# R303D.net
KiCad netlist of a schematic drawn in EAGLE
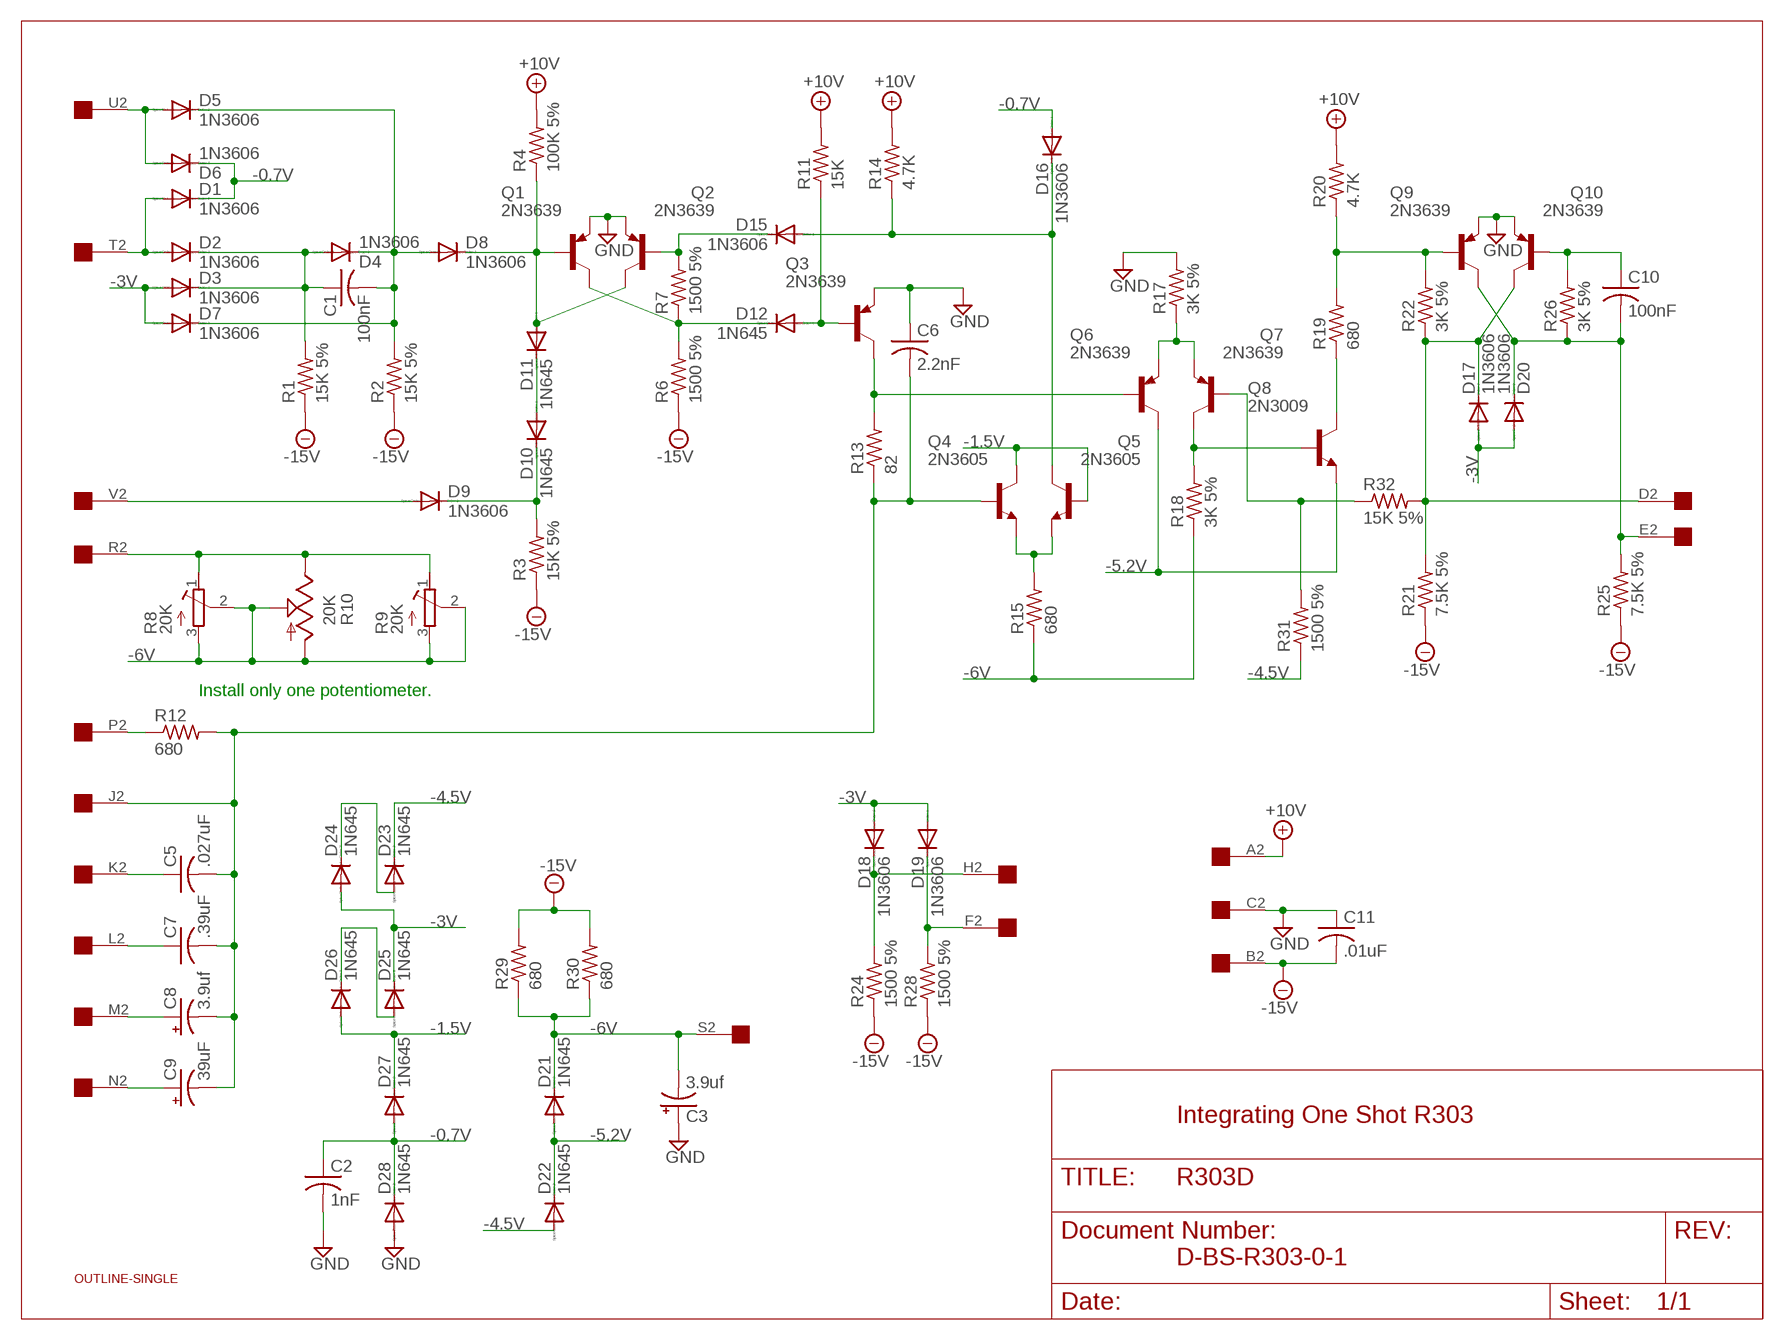
[diagram p0: schematic, sheet 1]

(export (version "E")
  (design (tool "Eeschema 10.0.6"))
  (components
    (comp (ref "C1")
      (value "100nF")
      (footprint "eagle-import:C075-032X103")
      (libsource (lib "eagle-import") (part "C-US075-032X103"))
    )
    (comp (ref "C2")
      (value "1nF")
      (footprint "eagle-import:C050-025X075")
      (libsource (lib "eagle-import") (part "C-US050-025X075"))
    )
    (comp (ref "C3")
      (value "3.9uf")
      (footprint "eagle-import:E12-4")
      (libsource (lib "eagle-import") (part "CPOL-USE12-4AXIAL"))
    )
    (comp (ref "C5")
      (value ".027uF")
      (footprint "eagle-import:C225-062X268")
      (libsource (lib "eagle-import") (part "C-US225-062X268"))
    )
    (comp (ref "C6")
      (value "2.2nF")
      (footprint "eagle-import:C050-025X075")
      (libsource (lib "eagle-import") (part "C-US050-025X075"))
    )
    (comp (ref "C7")
      (value ".39uF")
      (footprint "eagle-import:C325-137X374")
      (libsource (lib "eagle-import") (part "C-US325-137X374"))
    )
    (comp (ref "C8")
      (value "3.9uf")
      (footprint "eagle-import:E12-4")
      (libsource (lib "eagle-import") (part "CPOL-USE12-4AXIAL"))
    )
    (comp (ref "C9")
      (value "39uF")
      (footprint "eagle-import:E15-5")
      (libsource (lib "eagle-import") (part "CPOL-USE15-5AXIAL"))
    )
    (comp (ref "C10")
      (value "100nF")
      (footprint "eagle-import:C075-032X103")
      (libsource (lib "eagle-import") (part "C-US075-032X103"))
    )
    (comp (ref "C11")
      (value ".01uF")
      (footprint "eagle-import:C075-032X103")
      (libsource (lib "eagle-import") (part "C-US075-032X103"))
    )
    (comp (ref "D1")
      (value "1N3606")
      (footprint "eagle-import:DO35-10")
      (libsource (lib "eagle-import") (part "1N4148DO35-10"))
    )
    (comp (ref "D2")
      (value "1N3606")
      (footprint "eagle-import:DO35-10")
      (libsource (lib "eagle-import") (part "1N4148DO35-10"))
    )
    (comp (ref "D3")
      (value "1N3606")
      (footprint "eagle-import:DO35-10")
      (libsource (lib "eagle-import") (part "1N4148DO35-10"))
    )
    (comp (ref "D4")
      (value "1N3606")
      (footprint "eagle-import:DO35-10")
      (libsource (lib "eagle-import") (part "1N4148DO35-10"))
    )
    (comp (ref "D5")
      (value "1N3606")
      (footprint "eagle-import:DO35-10")
      (libsource (lib "eagle-import") (part "1N4148DO35-10"))
    )
    (comp (ref "D6")
      (value "1N3606")
      (footprint "eagle-import:DO35-10")
      (libsource (lib "eagle-import") (part "1N4148DO35-10"))
    )
    (comp (ref "D7")
      (value "1N3606")
      (footprint "eagle-import:DO35-10")
      (libsource (lib "eagle-import") (part "1N4148DO35-10"))
    )
    (comp (ref "D8")
      (value "1N3606")
      (footprint "eagle-import:DO35-10")
      (libsource (lib "eagle-import") (part "1N4148DO35-10"))
    )
    (comp (ref "D9")
      (value "1N3606")
      (footprint "eagle-import:DO35-10")
      (libsource (lib "eagle-import") (part "1N4148DO35-10"))
    )
    (comp (ref "D10")
      (value "1N645")
      (footprint "eagle-import:DO35-10")
      (libsource (lib "eagle-import") (part "1N4148DO35-10"))
    )
    (comp (ref "D11")
      (value "1N645")
      (footprint "eagle-import:DO35-10")
      (libsource (lib "eagle-import") (part "1N4148DO35-10"))
    )
    (comp (ref "D12")
      (value "1N645")
      (footprint "eagle-import:DO35-10")
      (libsource (lib "eagle-import") (part "1N4148DO35-10"))
    )
    (comp (ref "D15")
      (value "1N3606")
      (footprint "eagle-import:DO35-10")
      (libsource (lib "eagle-import") (part "1N4148DO35-10"))
    )
    (comp (ref "D16")
      (value "1N3606")
      (footprint "eagle-import:DO35-10")
      (libsource (lib "eagle-import") (part "1N4148DO35-10"))
    )
    (comp (ref "D17")
      (value "1N3606")
      (footprint "eagle-import:DO35-10")
      (libsource (lib "eagle-import") (part "1N4148DO35-10"))
    )
    (comp (ref "D18")
      (value "1N3606")
      (footprint "eagle-import:DO35-10")
      (libsource (lib "eagle-import") (part "1N4148DO35-10"))
    )
    (comp (ref "D19")
      (value "1N3606")
      (footprint "eagle-import:DO35-10")
      (libsource (lib "eagle-import") (part "1N4148DO35-10"))
    )
    (comp (ref "D20")
      (value "1N3606")
      (footprint "eagle-import:DO35-10")
      (libsource (lib "eagle-import") (part "1N4148DO35-10"))
    )
    (comp (ref "D21")
      (value "1N645")
      (footprint "eagle-import:DO35-10")
      (libsource (lib "eagle-import") (part "1N4148DO35-10"))
    )
    (comp (ref "D22")
      (value "1N645")
      (footprint "eagle-import:DO35-10")
      (libsource (lib "eagle-import") (part "1N4148DO35-10"))
    )
    (comp (ref "D23")
      (value "1N645")
      (footprint "eagle-import:DO35-10")
      (libsource (lib "eagle-import") (part "1N4148DO35-10"))
    )
    (comp (ref "D24")
      (value "1N645")
      (footprint "eagle-import:DO35-10")
      (libsource (lib "eagle-import") (part "1N4148DO35-10"))
    )
    (comp (ref "D25")
      (value "1N645")
      (footprint "eagle-import:DO35-10")
      (libsource (lib "eagle-import") (part "1N4148DO35-10"))
    )
    (comp (ref "D26")
      (value "1N645")
      (footprint "eagle-import:DO35-10")
      (libsource (lib "eagle-import") (part "1N4148DO35-10"))
    )
    (comp (ref "D27")
      (value "1N645")
      (footprint "eagle-import:DO35-10")
      (libsource (lib "eagle-import") (part "1N4148DO35-10"))
    )
    (comp (ref "D28")
      (value "1N645")
      (footprint "eagle-import:DO35-10")
      (libsource (lib "eagle-import") (part "1N4148DO35-10"))
    )
    (comp (ref "Q1")
      (value "2N3639")
      (footprint "eagle-import:TO39")
      (libsource (lib "eagle-import") (part "2N2904"))
    )
    (comp (ref "Q2")
      (value "2N3639")
      (footprint "eagle-import:TO39")
      (libsource (lib "eagle-import") (part "2N2904"))
    )
    (comp (ref "Q3")
      (value "2N3639")
      (footprint "eagle-import:TO39")
      (libsource (lib "eagle-import") (part "2N2904"))
    )
    (comp (ref "Q4")
      (value "2N3605")
      (footprint "eagle-import:TO5")
      (libsource (lib "eagle-import") (part "2N2102"))
    )
    (comp (ref "Q5")
      (value "2N3605")
      (footprint "eagle-import:TO5")
      (libsource (lib "eagle-import") (part "2N2102"))
    )
    (comp (ref "Q6")
      (value "2N3639")
      (footprint "eagle-import:TO39")
      (libsource (lib "eagle-import") (part "2N2904"))
    )
    (comp (ref "Q7")
      (value "2N3639")
      (footprint "eagle-import:TO39")
      (libsource (lib "eagle-import") (part "2N2904"))
    )
    (comp (ref "Q8")
      (value "2N3009")
      (footprint "eagle-import:TO5")
      (libsource (lib "eagle-import") (part "2N2102"))
    )
    (comp (ref "Q9")
      (value "2N3639")
      (footprint "eagle-import:TO39")
      (libsource (lib "eagle-import") (part "2N2904"))
    )
    (comp (ref "Q10")
      (value "2N3639")
      (footprint "eagle-import:TO39")
      (libsource (lib "eagle-import") (part "2N2904"))
    )
    (comp (ref "R1")
      (value "15K 5%")
      (footprint "eagle-import:0207_10")
      (libsource (lib "eagle-import") (part "R-US_0207/10"))
    )
    (comp (ref "R2")
      (value "15K 5%")
      (footprint "eagle-import:0207_10")
      (libsource (lib "eagle-import") (part "R-US_0207/10"))
    )
    (comp (ref "R3")
      (value "15K 5%")
      (footprint "eagle-import:0207_10")
      (libsource (lib "eagle-import") (part "R-US_0207/10"))
    )
    (comp (ref "R4")
      (value "100K 5%")
      (footprint "eagle-import:0207_10")
      (libsource (lib "eagle-import") (part "R-US_0207/10"))
    )
    (comp (ref "R6")
      (value "1500 5%")
      (footprint "eagle-import:0207_10")
      (libsource (lib "eagle-import") (part "R-US_0207/10"))
    )
    (comp (ref "R7")
      (value "1500 5%")
      (footprint "eagle-import:0207_10")
      (libsource (lib "eagle-import") (part "R-US_0207/10"))
    )
    (comp (ref "R8")
      (value "20K")
      (footprint "eagle-import:RTRIM43P")
      (libsource (lib "eagle-import") (part "R-TRIMM43P"))
    )
    (comp (ref "R9")
      (value "20K")
      (footprint "eagle-import:3006Y")
      (libsource (lib "eagle-import") (part "275P"))
    )
    (comp (ref "R10")
      (value "20K")
      (footprint "eagle-import:B25P")
      (libsource (lib "eagle-import") (part "TRIM_US-B25P"))
    )
    (comp (ref "R11")
      (value "15K")
      (footprint "eagle-import:0207_10")
      (libsource (lib "eagle-import") (part "R-US_0207/10"))
    )
    (comp (ref "R12")
      (value "680")
      (footprint "eagle-import:0207_10")
      (libsource (lib "eagle-import") (part "R-US_0207/10"))
    )
    (comp (ref "R13")
      (value "82")
      (footprint "eagle-import:0207_10")
      (libsource (lib "eagle-import") (part "R-US_0207/10"))
    )
    (comp (ref "R14")
      (value "4.7K")
      (footprint "eagle-import:0207_10")
      (libsource (lib "eagle-import") (part "R-US_0207/10"))
    )
    (comp (ref "R15")
      (value "680")
      (footprint "eagle-import:0207_10")
      (libsource (lib "eagle-import") (part "R-US_0207/10"))
    )
    (comp (ref "R17")
      (value "3K 5%")
      (footprint "eagle-import:0207_10")
      (libsource (lib "eagle-import") (part "R-US_0207/10"))
    )
    (comp (ref "R18")
      (value "3K 5%")
      (footprint "eagle-import:0207_10")
      (libsource (lib "eagle-import") (part "R-US_0207/10"))
    )
    (comp (ref "R19")
      (value "680")
      (footprint "eagle-import:0207_10")
      (libsource (lib "eagle-import") (part "R-US_0207/10"))
    )
    (comp (ref "R20")
      (value "4.7K")
      (footprint "eagle-import:0207_10")
      (libsource (lib "eagle-import") (part "R-US_0207/10"))
    )
    (comp (ref "R21")
      (value "7.5K 5%")
      (footprint "eagle-import:0207_10")
      (libsource (lib "eagle-import") (part "R-US_0207/10"))
    )
    (comp (ref "R22")
      (value "3K 5%")
      (footprint "eagle-import:0207_10")
      (libsource (lib "eagle-import") (part "R-US_0207/10"))
    )
    (comp (ref "R24")
      (value "1500 5%")
      (footprint "eagle-import:0207_10")
      (libsource (lib "eagle-import") (part "R-US_0207/10"))
    )
    (comp (ref "R25")
      (value "7.5K 5%")
      (footprint "eagle-import:0207_10")
      (libsource (lib "eagle-import") (part "R-US_0207/10"))
    )
    (comp (ref "R26")
      (value "3K 5%")
      (footprint "eagle-import:0207_10")
      (libsource (lib "eagle-import") (part "R-US_0207/10"))
    )
    (comp (ref "R28")
      (value "1500 5%")
      (footprint "eagle-import:0207_10")
      (libsource (lib "eagle-import") (part "R-US_0207/10"))
    )
    (comp (ref "R29")
      (value "680")
      (footprint "eagle-import:0207_10")
      (libsource (lib "eagle-import") (part "R-US_0207/10"))
    )
    (comp (ref "R30")
      (value "680")
      (footprint "eagle-import:0207_10")
      (libsource (lib "eagle-import") (part "R-US_0207/10"))
    )
    (comp (ref "R31")
      (value "1500 5%")
      (footprint "eagle-import:0207_10")
      (libsource (lib "eagle-import") (part "R-US_0207/10"))
    )
    (comp (ref "R32")
      (value "15K 5%")
      (footprint "eagle-import:0207_10")
      (libsource (lib "eagle-import") (part "R-US_0207/10"))
    )
    (comp (ref "U$1")
      (value "OUTLINE-SINGLE")
      (footprint "eagle-import:SINGLE")
      (libsource (lib "eagle-import") (part "OUTLINE-SINGLE"))
    )
    (comp (ref "U$2")
      (value "EDGE-1")
      (footprint "eagle-import:EDGE-CON1")
      (libsource (lib "eagle-import") (part "EDGE-1"))
    )
  )
  (nets
    (net (code "1") (name "+10V") (class "Default")
      (node (ref "R11") (pin "2") (pinfunction "2_2") (pintype "passive"))
      (node (ref "R14") (pin "2") (pinfunction "2_2") (pintype "passive"))
      (node (ref "R20") (pin "2") (pinfunction "2_2") (pintype "passive"))
      (node (ref "R4") (pin "2") (pinfunction "2_2") (pintype "passive"))
      (node (ref "U$2") (pin "A2") (pinfunction "1_A2") (pintype "bidirectional"))
    )
    (net (code "2") (name "-15V") (class "Default")
      (node (ref "C11") (pin "2") (pinfunction "2_2") (pintype "passive"))
      (node (ref "R1") (pin "1") (pinfunction "1_1") (pintype "passive"))
      (node (ref "R2") (pin "1") (pinfunction "1_1") (pintype "passive"))
      (node (ref "R21") (pin "1") (pinfunction "1_1") (pintype "passive"))
      (node (ref "R24") (pin "1") (pinfunction "1_1") (pintype "passive"))
      (node (ref "R25") (pin "1") (pinfunction "1_1") (pintype "passive"))
      (node (ref "R28") (pin "1") (pinfunction "1_1") (pintype "passive"))
      (node (ref "R29") (pin "2") (pinfunction "2_2") (pintype "passive"))
      (node (ref "R3") (pin "1") (pinfunction "1_1") (pintype "passive"))
      (node (ref "R30") (pin "2") (pinfunction "2_2") (pintype "passive"))
      (node (ref "R6") (pin "1") (pinfunction "1_1") (pintype "passive"))
      (node (ref "U$2") (pin "B2") (pinfunction "1_B2") (pintype "bidirectional"))
    )
    (net (code "3") (name "/-0.7V") (class "Default")
      (node (ref "C2") (pin "1") (pinfunction "1_1") (pintype "passive"))
      (node (ref "D1") (pin "C") (pinfunction "C_C") (pintype "passive"))
      (node (ref "D16") (pin "A") (pinfunction "A_A") (pintype "passive"))
      (node (ref "D27") (pin "A") (pinfunction "A_A") (pintype "passive"))
      (node (ref "D28") (pin "C") (pinfunction "C_C") (pintype "passive"))
      (node (ref "D6") (pin "C") (pinfunction "C_C") (pintype "passive"))
    )
    (net (code "4") (name "/-1.5V") (class "Default")
      (node (ref "D26") (pin "A") (pinfunction "A_A") (pintype "passive"))
      (node (ref "D27") (pin "C") (pinfunction "C_C") (pintype "passive"))
      (node (ref "Q4") (pin "3") (pinfunction "C_3") (pintype "passive"))
      (node (ref "Q5") (pin "2") (pinfunction "B_2") (pintype "passive"))
    )
    (net (code "5") (name "/-3V") (class "Default")
      (node (ref "D17") (pin "A") (pinfunction "A_A") (pintype "passive"))
      (node (ref "D18") (pin "A") (pinfunction "A_A") (pintype "passive"))
      (node (ref "D19") (pin "A") (pinfunction "A_A") (pintype "passive"))
      (node (ref "D20") (pin "A") (pinfunction "A_A") (pintype "passive"))
      (node (ref "D24") (pin "A") (pinfunction "A_A") (pintype "passive"))
      (node (ref "D25") (pin "C") (pinfunction "C_C") (pintype "passive"))
      (node (ref "D3") (pin "A") (pinfunction "A_A") (pintype "passive"))
      (node (ref "D7") (pin "A") (pinfunction "A_A") (pintype "passive"))
    )
    (net (code "6") (name "/-4.5V") (class "Default")
      (node (ref "D22") (pin "A") (pinfunction "A_A") (pintype "passive"))
      (node (ref "D23") (pin "C") (pinfunction "C_C") (pintype "passive"))
      (node (ref "R31") (pin "1") (pinfunction "1_1") (pintype "passive"))
    )
    (net (code "7") (name "/-5.2V") (class "Default")
      (node (ref "D21") (pin "A") (pinfunction "A_A") (pintype "passive"))
      (node (ref "D22") (pin "C") (pinfunction "C_C") (pintype "passive"))
      (node (ref "Q6") (pin "3") (pinfunction "C_3") (pintype "passive"))
      (node (ref "Q8") (pin "1") (pinfunction "E_1") (pintype "passive"))
    )
    (net (code "8") (name "/-6V") (class "Default")
      (node (ref "C3") (pin "-") (pinfunction "-_-") (pintype "passive"))
      (node (ref "D21") (pin "C") (pinfunction "C_C") (pintype "passive"))
      (node (ref "R10") (pin "A") (pinfunction "A_A") (pintype "passive"))
      (node (ref "R10") (pin "S") (pinfunction "S_S") (pintype "passive"))
      (node (ref "R15") (pin "1") (pinfunction "1_1") (pintype "passive"))
      (node (ref "R18") (pin "1") (pinfunction "1_1") (pintype "passive"))
      (node (ref "R29") (pin "1") (pinfunction "1_1") (pintype "passive"))
      (node (ref "R30") (pin "1") (pinfunction "1_1") (pintype "passive"))
      (node (ref "R8") (pin "2") (pinfunction "S_2") (pintype "passive"))
      (node (ref "R8") (pin "3") (pinfunction "A_3") (pintype "passive"))
      (node (ref "R9") (pin "2") (pinfunction "S_2") (pintype "passive"))
      (node (ref "R9") (pin "3") (pinfunction "E_3") (pintype "passive"))
      (node (ref "U$2") (pin "S2") (pinfunction "1_S2") (pintype "bidirectional"))
    )
    (net (code "9") (name "GND") (class "Default")
      (node (ref "C11") (pin "1") (pinfunction "1_1") (pintype "passive"))
      (node (ref "C2") (pin "2") (pinfunction "2_2") (pintype "passive"))
      (node (ref "C3") (pin "+") (pinfunction "+_+") (pintype "passive"))
      (node (ref "C6") (pin "1") (pinfunction "1_1") (pintype "passive"))
      (node (ref "D28") (pin "A") (pinfunction "A_A") (pintype "passive"))
      (node (ref "Q1") (pin "1") (pinfunction "E_1") (pintype "passive"))
      (node (ref "Q10") (pin "1") (pinfunction "E_1") (pintype "passive"))
      (node (ref "Q2") (pin "1") (pinfunction "E_1") (pintype "passive"))
      (node (ref "Q3") (pin "1") (pinfunction "E_1") (pintype "passive"))
      (node (ref "Q9") (pin "1") (pinfunction "E_1") (pintype "passive"))
      (node (ref "R17") (pin "2") (pinfunction "2_2") (pintype "passive"))
      (node (ref "U$2") (pin "C2") (pinfunction "1_C2") (pintype "bidirectional"))
    )
    (net (code "10") (name "Net-(C1-Pad1)") (class "Default")
      (node (ref "C1") (pin "1") (pinfunction "1_1") (pintype "passive"))
      (node (ref "D2") (pin "C") (pinfunction "C_C") (pintype "passive"))
      (node (ref "D3") (pin "C") (pinfunction "C_C") (pintype "passive"))
      (node (ref "D4") (pin "A") (pinfunction "A_A") (pintype "passive"))
      (node (ref "R1") (pin "2") (pinfunction "2_2") (pintype "passive"))
    )
    (net (code "11") (name "Net-(C1-Pad2)") (class "Default")
      (node (ref "C1") (pin "2") (pinfunction "2_2") (pintype "passive"))
      (node (ref "D4") (pin "C") (pinfunction "C_C") (pintype "passive"))
      (node (ref "D5") (pin "C") (pinfunction "C_C") (pintype "passive"))
      (node (ref "D7") (pin "C") (pinfunction "C_C") (pintype "passive"))
      (node (ref "D8") (pin "A") (pinfunction "A_A") (pintype "passive"))
      (node (ref "R2") (pin "2") (pinfunction "2_2") (pintype "passive"))
    )
    (net (code "12") (name "Net-(D10-PadA)") (class "Default")
      (node (ref "D10") (pin "A") (pinfunction "A_A") (pintype "passive"))
      (node (ref "D11") (pin "C") (pinfunction "C_C") (pintype "passive"))
    )
    (net (code "13") (name "Net-(D10-PadC)") (class "Default")
      (node (ref "D10") (pin "C") (pinfunction "C_C") (pintype "passive"))
      (node (ref "D9") (pin "C") (pinfunction "C_C") (pintype "passive"))
      (node (ref "R3") (pin "2") (pinfunction "2_2") (pintype "passive"))
    )
    (net (code "14") (name "Net-(D23-PadA)") (class "Default")
      (node (ref "D23") (pin "A") (pinfunction "A_A") (pintype "passive"))
      (node (ref "D24") (pin "C") (pinfunction "C_C") (pintype "passive"))
    )
    (net (code "15") (name "Net-(D25-PadA)") (class "Default")
      (node (ref "D25") (pin "A") (pinfunction "A_A") (pintype "passive"))
      (node (ref "D26") (pin "C") (pinfunction "C_C") (pintype "passive"))
    )
    (net (code "16") (name "Net-(Q1-B)") (class "Default")
      (node (ref "D11") (pin "A") (pinfunction "A_A") (pintype "passive"))
      (node (ref "D8") (pin "C") (pinfunction "C_C") (pintype "passive"))
      (node (ref "Q1") (pin "2") (pinfunction "B_2") (pintype "passive"))
      (node (ref "Q2") (pin "3") (pinfunction "C_3") (pintype "passive"))
      (node (ref "R4") (pin "1") (pinfunction "1_1") (pintype "passive"))
    )
    (net (code "17") (name "Net-(Q1-C)") (class "Default")
      (node (ref "D12") (pin "C") (pinfunction "C_C") (pintype "passive"))
      (node (ref "Q1") (pin "3") (pinfunction "C_3") (pintype "passive"))
      (node (ref "R6") (pin "2") (pinfunction "2_2") (pintype "passive"))
      (node (ref "R7") (pin "1") (pinfunction "1_1") (pintype "passive"))
    )
    (net (code "18") (name "Net-(Q2-B)") (class "Default")
      (node (ref "D15") (pin "C") (pinfunction "C_C") (pintype "passive"))
      (node (ref "Q2") (pin "2") (pinfunction "B_2") (pintype "passive"))
      (node (ref "R7") (pin "2") (pinfunction "2_2") (pintype "passive"))
    )
    (net (code "19") (name "Net-(Q3-B)") (class "Default")
      (node (ref "D12") (pin "A") (pinfunction "A_A") (pintype "passive"))
      (node (ref "Q3") (pin "2") (pinfunction "B_2") (pintype "passive"))
      (node (ref "R11") (pin "1") (pinfunction "1_1") (pintype "passive"))
    )
    (net (code "20") (name "Net-(Q3-C)") (class "Default")
      (node (ref "Q3") (pin "3") (pinfunction "C_3") (pintype "passive"))
      (node (ref "Q6") (pin "2") (pinfunction "B_2") (pintype "passive"))
      (node (ref "R13") (pin "2") (pinfunction "2_2") (pintype "passive"))
    )
    (net (code "21") (name "Net-(Q4-B)") (class "Default")
      (node (ref "C5") (pin "2") (pinfunction "2_2") (pintype "passive"))
      (node (ref "C6") (pin "2") (pinfunction "2_2") (pintype "passive"))
      (node (ref "C7") (pin "2") (pinfunction "2_2") (pintype "passive"))
      (node (ref "C8") (pin "-") (pinfunction "-_-") (pintype "passive"))
      (node (ref "C9") (pin "-") (pinfunction "-_-") (pintype "passive"))
      (node (ref "Q4") (pin "2") (pinfunction "B_2") (pintype "passive"))
      (node (ref "R12") (pin "2") (pinfunction "2_2") (pintype "passive"))
      (node (ref "R13") (pin "1") (pinfunction "1_1") (pintype "passive"))
      (node (ref "U$2") (pin "J2") (pinfunction "1_J2") (pintype "bidirectional"))
    )
    (net (code "22") (name "Net-(Q4-E)") (class "Default")
      (node (ref "Q4") (pin "1") (pinfunction "E_1") (pintype "passive"))
      (node (ref "Q5") (pin "1") (pinfunction "E_1") (pintype "passive"))
      (node (ref "R15") (pin "2") (pinfunction "2_2") (pintype "passive"))
    )
    (net (code "23") (name "Net-(Q5-C)") (class "Default")
      (node (ref "D15") (pin "A") (pinfunction "A_A") (pintype "passive"))
      (node (ref "D16") (pin "C") (pinfunction "C_C") (pintype "passive"))
      (node (ref "Q5") (pin "3") (pinfunction "C_3") (pintype "passive"))
      (node (ref "R14") (pin "1") (pinfunction "1_1") (pintype "passive"))
    )
    (net (code "24") (name "Net-(Q6-E)") (class "Default")
      (node (ref "Q6") (pin "1") (pinfunction "E_1") (pintype "passive"))
      (node (ref "Q7") (pin "1") (pinfunction "E_1") (pintype "passive"))
      (node (ref "R17") (pin "1") (pinfunction "1_1") (pintype "passive"))
    )
    (net (code "25") (name "Net-(Q7-B)") (class "Default")
      (node (ref "Q7") (pin "2") (pinfunction "B_2") (pintype "passive"))
      (node (ref "R31") (pin "2") (pinfunction "2_2") (pintype "passive"))
      (node (ref "R32") (pin "1") (pinfunction "1_1") (pintype "passive"))
    )
    (net (code "26") (name "Net-(Q7-C)") (class "Default")
      (node (ref "Q7") (pin "3") (pinfunction "C_3") (pintype "passive"))
      (node (ref "Q8") (pin "2") (pinfunction "B_2") (pintype "passive"))
      (node (ref "R18") (pin "2") (pinfunction "2_2") (pintype "passive"))
    )
    (net (code "27") (name "Net-(Q8-C)") (class "Default")
      (node (ref "Q8") (pin "3") (pinfunction "C_3") (pintype "passive"))
      (node (ref "R19") (pin "1") (pinfunction "1_1") (pintype "passive"))
    )
    (net (code "28") (name "Net-(Q9-B)") (class "Default")
      (node (ref "Q9") (pin "2") (pinfunction "B_2") (pintype "passive"))
      (node (ref "R19") (pin "2") (pinfunction "2_2") (pintype "passive"))
      (node (ref "R20") (pin "1") (pinfunction "1_1") (pintype "passive"))
      (node (ref "R22") (pin "2") (pinfunction "2_2") (pintype "passive"))
    )
    (net (code "29") (name "Net-(Q9-C)") (class "Default")
      (node (ref "C10") (pin "2") (pinfunction "2_2") (pintype "passive"))
      (node (ref "D20") (pin "C") (pinfunction "C_C") (pintype "passive"))
      (node (ref "Q9") (pin "3") (pinfunction "C_3") (pintype "passive"))
      (node (ref "R25") (pin "2") (pinfunction "2_2") (pintype "passive"))
      (node (ref "R26") (pin "1") (pinfunction "1_1") (pintype "passive"))
      (node (ref "U$2") (pin "E2") (pinfunction "1_E2") (pintype "bidirectional"))
    )
    (net (code "30") (name "Net-(Q10-B)") (class "Default")
      (node (ref "C10") (pin "1") (pinfunction "1_1") (pintype "passive"))
      (node (ref "Q10") (pin "2") (pinfunction "B_2") (pintype "passive"))
      (node (ref "R26") (pin "2") (pinfunction "2_2") (pintype "passive"))
    )
    (net (code "31") (name "Net-(Q10-C)") (class "Default")
      (node (ref "D17") (pin "C") (pinfunction "C_C") (pintype "passive"))
      (node (ref "Q10") (pin "3") (pinfunction "C_3") (pintype "passive"))
      (node (ref "R21") (pin "2") (pinfunction "2_2") (pintype "passive"))
      (node (ref "R22") (pin "1") (pinfunction "1_1") (pintype "passive"))
      (node (ref "R32") (pin "2") (pinfunction "2_2") (pintype "passive"))
      (node (ref "U$2") (pin "D2") (pinfunction "1_D2") (pintype "bidirectional"))
    )
    (net (code "32") (name "Net-(R8-E)") (class "Default")
      (node (ref "R10") (pin "E") (pinfunction "E_E") (pintype "passive"))
      (node (ref "R8") (pin "1") (pinfunction "E_1") (pintype "passive"))
      (node (ref "R9") (pin "1") (pinfunction "A_1") (pintype "passive"))
      (node (ref "U$2") (pin "R2") (pinfunction "1_R2") (pintype "bidirectional"))
    )
    (net (code "33") (name "Net-(U$2F-1)") (class "Default")
      (node (ref "D19") (pin "C") (pinfunction "C_C") (pintype "passive"))
      (node (ref "R28") (pin "2") (pinfunction "2_2") (pintype "passive"))
      (node (ref "U$2") (pin "F2") (pinfunction "1_F2") (pintype "bidirectional"))
    )
    (net (code "34") (name "Net-(U$2G-1)") (class "Default")
      (node (ref "D18") (pin "C") (pinfunction "C_C") (pintype "passive"))
      (node (ref "R24") (pin "2") (pinfunction "2_2") (pintype "passive"))
      (node (ref "U$2") (pin "H2") (pinfunction "1_H2") (pintype "bidirectional"))
    )
    (net (code "35") (name "Net-(U$2I-1)") (class "Default")
      (node (ref "C5") (pin "1") (pinfunction "1_1") (pintype "passive"))
      (node (ref "U$2") (pin "K2") (pinfunction "1_K2") (pintype "bidirectional"))
    )
    (net (code "36") (name "Net-(U$2J-1)") (class "Default")
      (node (ref "C7") (pin "1") (pinfunction "1_1") (pintype "passive"))
      (node (ref "U$2") (pin "L2") (pinfunction "1_L2") (pintype "bidirectional"))
    )
    (net (code "37") (name "Net-(U$2K-1)") (class "Default")
      (node (ref "C8") (pin "+") (pinfunction "+_+") (pintype "passive"))
      (node (ref "U$2") (pin "M2") (pinfunction "1_M2") (pintype "bidirectional"))
    )
    (net (code "38") (name "Net-(U$2L-1)") (class "Default")
      (node (ref "C9") (pin "+") (pinfunction "+_+") (pintype "passive"))
      (node (ref "U$2") (pin "N2") (pinfunction "1_N2") (pintype "bidirectional"))
    )
    (net (code "39") (name "Net-(U$2M-1)") (class "Default")
      (node (ref "R12") (pin "1") (pinfunction "1_1") (pintype "passive"))
      (node (ref "U$2") (pin "P2") (pinfunction "1_P2") (pintype "bidirectional"))
    )
    (net (code "40") (name "Net-(U$2P-1)") (class "Default")
      (node (ref "D1") (pin "A") (pinfunction "A_A") (pintype "passive"))
      (node (ref "D2") (pin "A") (pinfunction "A_A") (pintype "passive"))
      (node (ref "U$2") (pin "T2") (pinfunction "1_T2") (pintype "bidirectional"))
    )
    (net (code "41") (name "Net-(U$2Q-1)") (class "Default")
      (node (ref "D5") (pin "A") (pinfunction "A_A") (pintype "passive"))
      (node (ref "D6") (pin "A") (pinfunction "A_A") (pintype "passive"))
      (node (ref "U$2") (pin "U2") (pinfunction "1_U2") (pintype "bidirectional"))
    )
    (net (code "42") (name "Net-(U$2R-1)") (class "Default")
      (node (ref "D9") (pin "A") (pinfunction "A_A") (pintype "passive"))
      (node (ref "U$2") (pin "V2") (pinfunction "1_V2") (pintype "bidirectional"))
    )
  )
)
